# QSPI.net
KiCad netlist of a schematic drawn in Altium Designer
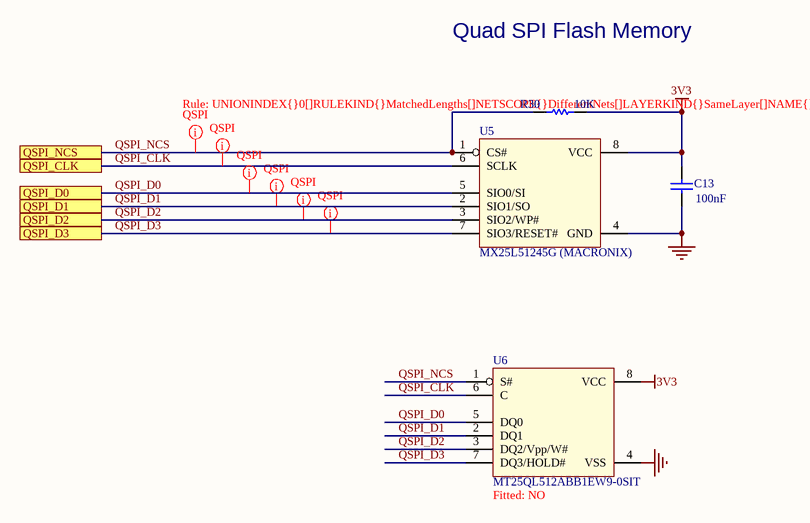
[diagram p0: QSPI.SchDoc]

(export (version "E")
  (design (tool "Eeschema 10.0.6"))
  (components
    (comp (ref "C13")
      (value "100nF")
      (footprint "0402C")
      (description "Capacitor,100nF,16V,X7R,10%,0402,YAGEO")
      (libsource (lib "MCD_TOOLS") (part "Cap_100nF_X7R_10%_0402"))
    )
    (comp (ref "R30")
      (value "10K")
      (footprint "0402R")
      (description "Resistor,10K,0402,1%,YAGEO")
      (libsource (lib "MCD_TOOLS") (part "Res_10K_1%_0402"))
    )
    (comp (ref "U5")
      (value "MX25L51245G (MACRONIX)")
      (footprint "SON8_1R27_6X8")
      (description "512Mb, 3V, Multiple I/O Serial Flash Memory, Quad/Dual")
      (fields (field (name "PROVIDED") "Subcon"))
      (libsource (lib "MCD_TOOLS_MISCELLANEOUS") (part "MX25L51245G"))
    )
    (comp (ref "U6")
      (value "MT25QL512ABB1EW9-0SIT")
      (footprint "DFN8_1R27_6X8_TP4R6X5R3")
      (description "512Mb, 3V, Multiple I/O Serial Flash Memory, Quad/Dual")
      (fields (field (name "FITTED") "NO"))
      (libsource (lib "MCD_TOOLS_MISCELLANEOUS") (part "N25Q512A13GF840E"))
    )
  )
  (nets
    (net (code "1") (name "/QSPI_CLK") (class "Default")
      (node (ref "U5") (pin "6") (pinfunction "SCLK_6") (pintype "passive"))
      (node (ref "U6") (pin "6") (pinfunction "C_6") (pintype "passive"))
    )
    (net (code "2") (name "/QSPI_D0") (class "Default")
      (node (ref "U5") (pin "5") (pinfunction "SIO0/SI_5") (pintype "passive"))
      (node (ref "U6") (pin "5") (pinfunction "DQ0_5") (pintype "passive"))
    )
    (net (code "3") (name "/QSPI_D1") (class "Default")
      (node (ref "U5") (pin "2") (pinfunction "SIO1/SO_2") (pintype "passive"))
      (node (ref "U6") (pin "2") (pinfunction "DQ1_2") (pintype "passive"))
    )
    (net (code "4") (name "/QSPI_D2") (class "Default")
      (node (ref "U5") (pin "3") (pinfunction "SIO2/WP#_3") (pintype "passive"))
      (node (ref "U6") (pin "3") (pinfunction "DQ2/Vpp/W#_3") (pintype "passive"))
    )
    (net (code "5") (name "/QSPI_D3") (class "Default")
      (node (ref "U5") (pin "7") (pinfunction "SIO3/RESET#_7") (pintype "passive"))
      (node (ref "U6") (pin "7") (pinfunction "DQ3/HOLD#_7") (pintype "passive"))
    )
    (net (code "6") (name "/QSPI_NCS") (class "Default")
      (node (ref "R30") (pin "1") (pinfunction "1_1") (pintype "passive"))
      (node (ref "U5") (pin "1") (pinfunction "CS#_1") (pintype "passive"))
      (node (ref "U6") (pin "1") (pinfunction "S#_1") (pintype "passive"))
    )
    (net (code "7") (name "3V3") (class "Default")
      (node (ref "C13") (pin "2") (pinfunction "2_2") (pintype "passive"))
      (node (ref "R30") (pin "2") (pinfunction "2_2") (pintype "passive"))
      (node (ref "U5") (pin "8") (pinfunction "VCC_8") (pintype "passive"))
      (node (ref "U6") (pin "8") (pinfunction "VCC_8") (pintype "passive"))
    )
    (net (code "8") (name "GND") (class "Default")
      (node (ref "C13") (pin "1") (pinfunction "1_1") (pintype "passive"))
      (node (ref "U5") (pin "4") (pinfunction "GND_4") (pintype "passive"))
      (node (ref "U6") (pin "4") (pinfunction "VSS_4") (pintype "passive"))
    )
  )
)
